# 16-BitSWStatusLed.net
KiCad netlist of a schematic drawn in Altium Designer
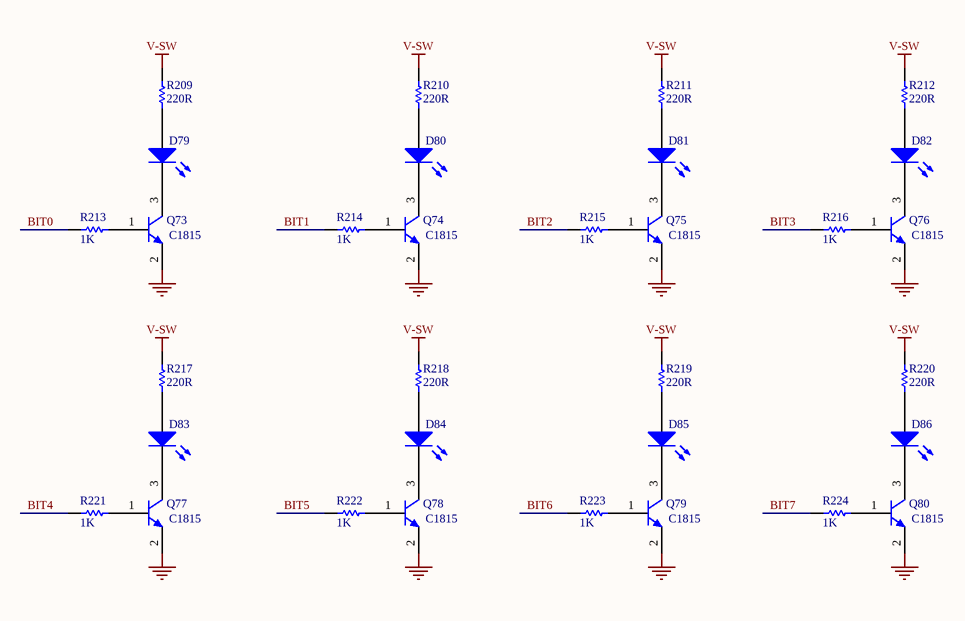
[diagram p0: 16-BitSWStatusLed.SchDoc]

(export (version "E")
  (design (tool "Eeschema 10.0.6"))
  (components
    (comp (ref "D79")
      (value "LED")
      (footprint "LED-3528")
      (description "Typical RED, GREEN, YELLOW, AMBER GaAs LED")
      (fields (field (name "PUBLISHER") "Altium Limited"))
      (libsource (lib "Miscellaneous Devices") (part "LED2"))
    )
    (comp (ref "D80")
      (value "LED")
      (footprint "LED-3528")
      (description "Typical RED, GREEN, YELLOW, AMBER GaAs LED")
      (fields (field (name "PUBLISHER") "Altium Limited"))
      (libsource (lib "Miscellaneous Devices") (part "LED2"))
    )
    (comp (ref "D81")
      (value "LED")
      (footprint "LED-3528")
      (description "Typical RED, GREEN, YELLOW, AMBER GaAs LED")
      (fields (field (name "PUBLISHER") "Altium Limited"))
      (libsource (lib "Miscellaneous Devices") (part "LED2"))
    )
    (comp (ref "D82")
      (value "LED")
      (footprint "LED-3528")
      (description "Typical RED, GREEN, YELLOW, AMBER GaAs LED")
      (fields (field (name "PUBLISHER") "Altium Limited"))
      (libsource (lib "Miscellaneous Devices") (part "LED2"))
    )
    (comp (ref "D83")
      (value "LED")
      (footprint "LED-3528")
      (description "Typical RED, GREEN, YELLOW, AMBER GaAs LED")
      (fields (field (name "PUBLISHER") "Altium Limited"))
      (libsource (lib "Miscellaneous Devices") (part "LED2"))
    )
    (comp (ref "D84")
      (value "LED")
      (footprint "LED-3528")
      (description "Typical RED, GREEN, YELLOW, AMBER GaAs LED")
      (fields (field (name "PUBLISHER") "Altium Limited"))
      (libsource (lib "Miscellaneous Devices") (part "LED2"))
    )
    (comp (ref "D85")
      (value "LED")
      (footprint "LED-3528")
      (description "Typical RED, GREEN, YELLOW, AMBER GaAs LED")
      (fields (field (name "PUBLISHER") "Altium Limited"))
      (libsource (lib "Miscellaneous Devices") (part "LED2"))
    )
    (comp (ref "D86")
      (value "LED")
      (footprint "LED-3528")
      (description "Typical RED, GREEN, YELLOW, AMBER GaAs LED")
      (fields (field (name "PUBLISHER") "Altium Limited"))
      (libsource (lib "Miscellaneous Devices") (part "LED2"))
    )
    (comp (ref "Q73")
      (value "C1815")
      (footprint "SOT23-321")
      (description "NPN Bipolar Transistor")
      (fields (field (name "Comment") "C1815-SMD"))
      (libsource (lib "Miscellaneous Devices") (part "NPN"))
    )
    (comp (ref "Q74")
      (value "C1815")
      (footprint "SOT23-321")
      (description "NPN Bipolar Transistor")
      (fields (field (name "Comment") "C1815-SMD"))
      (libsource (lib "Miscellaneous Devices") (part "NPN"))
    )
    (comp (ref "Q75")
      (value "C1815")
      (footprint "SOT23-321")
      (description "NPN Bipolar Transistor")
      (fields (field (name "Comment") "C1815-SMD"))
      (libsource (lib "Miscellaneous Devices") (part "NPN"))
    )
    (comp (ref "Q76")
      (value "C1815")
      (footprint "SOT23-321")
      (description "NPN Bipolar Transistor")
      (fields (field (name "Comment") "C1815-SMD"))
      (libsource (lib "Miscellaneous Devices") (part "NPN"))
    )
    (comp (ref "Q77")
      (value "C1815")
      (footprint "SOT23-321")
      (description "NPN Bipolar Transistor")
      (fields (field (name "Comment") "C1815-SMD"))
      (libsource (lib "Miscellaneous Devices") (part "NPN"))
    )
    (comp (ref "Q78")
      (value "C1815")
      (footprint "SOT23-321")
      (description "NPN Bipolar Transistor")
      (fields (field (name "Comment") "C1815-SMD"))
      (libsource (lib "Miscellaneous Devices") (part "NPN"))
    )
    (comp (ref "Q79")
      (value "C1815")
      (footprint "SOT23-321")
      (description "NPN Bipolar Transistor")
      (fields (field (name "Comment") "C1815-SMD"))
      (libsource (lib "Miscellaneous Devices") (part "NPN"))
    )
    (comp (ref "Q80")
      (value "C1815")
      (footprint "SOT23-321")
      (description "NPN Bipolar Transistor")
      (fields (field (name "Comment") "C1815-SMD"))
      (libsource (lib "Miscellaneous Devices") (part "NPN"))
    )
    (comp (ref "R209")
      (value "220R")
      (footprint "R-0805")
      (description "Resistor")
      (fields (field (name "Comment") "221") (field (name "PUBLISHER") "Altium Limited"))
      (libsource (lib "Miscellaneous Devices") (part "Res1"))
    )
    (comp (ref "R210")
      (value "220R")
      (footprint "R-0805")
      (description "Resistor")
      (fields (field (name "Comment") "221") (field (name "PUBLISHER") "Altium Limited"))
      (libsource (lib "Miscellaneous Devices") (part "Res1"))
    )
    (comp (ref "R211")
      (value "220R")
      (footprint "R-0805")
      (description "Resistor")
      (fields (field (name "Comment") "221") (field (name "PUBLISHER") "Altium Limited"))
      (libsource (lib "Miscellaneous Devices") (part "Res1"))
    )
    (comp (ref "R212")
      (value "220R")
      (footprint "R-0805")
      (description "Resistor")
      (fields (field (name "Comment") "221") (field (name "PUBLISHER") "Altium Limited"))
      (libsource (lib "Miscellaneous Devices") (part "Res1"))
    )
    (comp (ref "R213")
      (value "1K")
      (footprint "R-0805")
      (description "Resistor")
      (fields (field (name "PUBLISHER") "Altium Limited"))
      (libsource (lib "Miscellaneous Devices") (part "Res1"))
    )
    (comp (ref "R214")
      (value "1K")
      (footprint "R-0805")
      (description "Resistor")
      (fields (field (name "PUBLISHER") "Altium Limited"))
      (libsource (lib "Miscellaneous Devices") (part "Res1"))
    )
    (comp (ref "R215")
      (value "1K")
      (footprint "R-0805")
      (description "Resistor")
      (fields (field (name "PUBLISHER") "Altium Limited"))
      (libsource (lib "Miscellaneous Devices") (part "Res1"))
    )
    (comp (ref "R216")
      (value "1K")
      (footprint "R-0805")
      (description "Resistor")
      (fields (field (name "PUBLISHER") "Altium Limited"))
      (libsource (lib "Miscellaneous Devices") (part "Res1"))
    )
    (comp (ref "R217")
      (value "220R")
      (footprint "R-0805")
      (description "Resistor")
      (fields (field (name "Comment") "221") (field (name "PUBLISHER") "Altium Limited"))
      (libsource (lib "Miscellaneous Devices") (part "Res1"))
    )
    (comp (ref "R218")
      (value "220R")
      (footprint "R-0805")
      (description "Resistor")
      (fields (field (name "Comment") "221") (field (name "PUBLISHER") "Altium Limited"))
      (libsource (lib "Miscellaneous Devices") (part "Res1"))
    )
    (comp (ref "R219")
      (value "220R")
      (footprint "R-0805")
      (description "Resistor")
      (fields (field (name "Comment") "221") (field (name "PUBLISHER") "Altium Limited"))
      (libsource (lib "Miscellaneous Devices") (part "Res1"))
    )
    (comp (ref "R220")
      (value "220R")
      (footprint "R-0805")
      (description "Resistor")
      (fields (field (name "Comment") "221") (field (name "PUBLISHER") "Altium Limited"))
      (libsource (lib "Miscellaneous Devices") (part "Res1"))
    )
    (comp (ref "R221")
      (value "1K")
      (footprint "R-0805")
      (description "Resistor")
      (fields (field (name "PUBLISHER") "Altium Limited"))
      (libsource (lib "Miscellaneous Devices") (part "Res1"))
    )
    (comp (ref "R222")
      (value "1K")
      (footprint "R-0805")
      (description "Resistor")
      (fields (field (name "PUBLISHER") "Altium Limited"))
      (libsource (lib "Miscellaneous Devices") (part "Res1"))
    )
    (comp (ref "R223")
      (value "1K")
      (footprint "R-0805")
      (description "Resistor")
      (fields (field (name "PUBLISHER") "Altium Limited"))
      (libsource (lib "Miscellaneous Devices") (part "Res1"))
    )
    (comp (ref "R224")
      (value "1K")
      (footprint "R-0805")
      (description "Resistor")
      (fields (field (name "PUBLISHER") "Altium Limited"))
      (libsource (lib "Miscellaneous Devices") (part "Res1"))
    )
  )
  (nets
    (net (code "1") (name "/BIT0") (class "Default")
      (node (ref "R213") (pin "2") (pinfunction "2_2") (pintype "passive"))
    )
    (net (code "2") (name "/BIT1") (class "Default")
      (node (ref "R214") (pin "2") (pinfunction "2_2") (pintype "passive"))
    )
    (net (code "3") (name "/BIT2") (class "Default")
      (node (ref "R215") (pin "2") (pinfunction "2_2") (pintype "passive"))
    )
    (net (code "4") (name "/BIT3") (class "Default")
      (node (ref "R216") (pin "2") (pinfunction "2_2") (pintype "passive"))
    )
    (net (code "5") (name "/BIT4") (class "Default")
      (node (ref "R221") (pin "2") (pinfunction "2_2") (pintype "passive"))
    )
    (net (code "6") (name "/BIT5") (class "Default")
      (node (ref "R222") (pin "2") (pinfunction "2_2") (pintype "passive"))
    )
    (net (code "7") (name "/BIT6") (class "Default")
      (node (ref "R223") (pin "2") (pinfunction "2_2") (pintype "passive"))
    )
    (net (code "8") (name "/BIT7") (class "Default")
      (node (ref "R224") (pin "2") (pinfunction "2_2") (pintype "passive"))
    )
    (net (code "9") (name "GND") (class "Default")
      (node (ref "Q73") (pin "2") (pinfunction "E_2") (pintype "passive"))
      (node (ref "Q74") (pin "2") (pinfunction "E_2") (pintype "passive"))
      (node (ref "Q75") (pin "2") (pinfunction "E_2") (pintype "passive"))
      (node (ref "Q76") (pin "2") (pinfunction "E_2") (pintype "passive"))
      (node (ref "Q77") (pin "2") (pinfunction "E_2") (pintype "passive"))
      (node (ref "Q78") (pin "2") (pinfunction "E_2") (pintype "passive"))
      (node (ref "Q79") (pin "2") (pinfunction "E_2") (pintype "passive"))
      (node (ref "Q80") (pin "2") (pinfunction "E_2") (pintype "passive"))
    )
    (net (code "10") (name "Net-(D79-A)") (class "Default")
      (node (ref "D79") (pin "1") (pinfunction "A_1") (pintype "passive"))
      (node (ref "R209") (pin "1") (pinfunction "1_1") (pintype "passive"))
    )
    (net (code "11") (name "Net-(D79-K)") (class "Default")
      (node (ref "D79") (pin "2") (pinfunction "K_2") (pintype "passive"))
      (node (ref "Q73") (pin "3") (pinfunction "C_3") (pintype "passive"))
    )
    (net (code "12") (name "Net-(D80-A)") (class "Default")
      (node (ref "D80") (pin "1") (pinfunction "A_1") (pintype "passive"))
      (node (ref "R210") (pin "1") (pinfunction "1_1") (pintype "passive"))
    )
    (net (code "13") (name "Net-(D80-K)") (class "Default")
      (node (ref "D80") (pin "2") (pinfunction "K_2") (pintype "passive"))
      (node (ref "Q74") (pin "3") (pinfunction "C_3") (pintype "passive"))
    )
    (net (code "14") (name "Net-(D81-A)") (class "Default")
      (node (ref "D81") (pin "1") (pinfunction "A_1") (pintype "passive"))
      (node (ref "R211") (pin "1") (pinfunction "1_1") (pintype "passive"))
    )
    (net (code "15") (name "Net-(D81-K)") (class "Default")
      (node (ref "D81") (pin "2") (pinfunction "K_2") (pintype "passive"))
      (node (ref "Q75") (pin "3") (pinfunction "C_3") (pintype "passive"))
    )
    (net (code "16") (name "Net-(D82-A)") (class "Default")
      (node (ref "D82") (pin "1") (pinfunction "A_1") (pintype "passive"))
      (node (ref "R212") (pin "1") (pinfunction "1_1") (pintype "passive"))
    )
    (net (code "17") (name "Net-(D82-K)") (class "Default")
      (node (ref "D82") (pin "2") (pinfunction "K_2") (pintype "passive"))
      (node (ref "Q76") (pin "3") (pinfunction "C_3") (pintype "passive"))
    )
    (net (code "18") (name "Net-(D83-A)") (class "Default")
      (node (ref "D83") (pin "1") (pinfunction "A_1") (pintype "passive"))
      (node (ref "R217") (pin "1") (pinfunction "1_1") (pintype "passive"))
    )
    (net (code "19") (name "Net-(D83-K)") (class "Default")
      (node (ref "D83") (pin "2") (pinfunction "K_2") (pintype "passive"))
      (node (ref "Q77") (pin "3") (pinfunction "C_3") (pintype "passive"))
    )
    (net (code "20") (name "Net-(D84-A)") (class "Default")
      (node (ref "D84") (pin "1") (pinfunction "A_1") (pintype "passive"))
      (node (ref "R218") (pin "1") (pinfunction "1_1") (pintype "passive"))
    )
    (net (code "21") (name "Net-(D84-K)") (class "Default")
      (node (ref "D84") (pin "2") (pinfunction "K_2") (pintype "passive"))
      (node (ref "Q78") (pin "3") (pinfunction "C_3") (pintype "passive"))
    )
    (net (code "22") (name "Net-(D85-A)") (class "Default")
      (node (ref "D85") (pin "1") (pinfunction "A_1") (pintype "passive"))
      (node (ref "R219") (pin "1") (pinfunction "1_1") (pintype "passive"))
    )
    (net (code "23") (name "Net-(D85-K)") (class "Default")
      (node (ref "D85") (pin "2") (pinfunction "K_2") (pintype "passive"))
      (node (ref "Q79") (pin "3") (pinfunction "C_3") (pintype "passive"))
    )
    (net (code "24") (name "Net-(D86-A)") (class "Default")
      (node (ref "D86") (pin "1") (pinfunction "A_1") (pintype "passive"))
      (node (ref "R220") (pin "1") (pinfunction "1_1") (pintype "passive"))
    )
    (net (code "25") (name "Net-(D86-K)") (class "Default")
      (node (ref "D86") (pin "2") (pinfunction "K_2") (pintype "passive"))
      (node (ref "Q80") (pin "3") (pinfunction "C_3") (pintype "passive"))
    )
    (net (code "26") (name "Net-(Q73-B)") (class "Default")
      (node (ref "Q73") (pin "1") (pinfunction "B_1") (pintype "passive"))
      (node (ref "R213") (pin "1") (pinfunction "1_1") (pintype "passive"))
    )
    (net (code "27") (name "Net-(Q74-B)") (class "Default")
      (node (ref "Q74") (pin "1") (pinfunction "B_1") (pintype "passive"))
      (node (ref "R214") (pin "1") (pinfunction "1_1") (pintype "passive"))
    )
    (net (code "28") (name "Net-(Q75-B)") (class "Default")
      (node (ref "Q75") (pin "1") (pinfunction "B_1") (pintype "passive"))
      (node (ref "R215") (pin "1") (pinfunction "1_1") (pintype "passive"))
    )
    (net (code "29") (name "Net-(Q76-B)") (class "Default")
      (node (ref "Q76") (pin "1") (pinfunction "B_1") (pintype "passive"))
      (node (ref "R216") (pin "1") (pinfunction "1_1") (pintype "passive"))
    )
    (net (code "30") (name "Net-(Q77-B)") (class "Default")
      (node (ref "Q77") (pin "1") (pinfunction "B_1") (pintype "passive"))
      (node (ref "R221") (pin "1") (pinfunction "1_1") (pintype "passive"))
    )
    (net (code "31") (name "Net-(Q78-B)") (class "Default")
      (node (ref "Q78") (pin "1") (pinfunction "B_1") (pintype "passive"))
      (node (ref "R222") (pin "1") (pinfunction "1_1") (pintype "passive"))
    )
    (net (code "32") (name "Net-(Q79-B)") (class "Default")
      (node (ref "Q79") (pin "1") (pinfunction "B_1") (pintype "passive"))
      (node (ref "R223") (pin "1") (pinfunction "1_1") (pintype "passive"))
    )
    (net (code "33") (name "Net-(Q80-B)") (class "Default")
      (node (ref "Q80") (pin "1") (pinfunction "B_1") (pintype "passive"))
      (node (ref "R224") (pin "1") (pinfunction "1_1") (pintype "passive"))
    )
    (net (code "34") (name "V-SW") (class "Default")
      (node (ref "R209") (pin "2") (pinfunction "2_2") (pintype "passive"))
      (node (ref "R210") (pin "2") (pinfunction "2_2") (pintype "passive"))
      (node (ref "R211") (pin "2") (pinfunction "2_2") (pintype "passive"))
      (node (ref "R212") (pin "2") (pinfunction "2_2") (pintype "passive"))
      (node (ref "R217") (pin "2") (pinfunction "2_2") (pintype "passive"))
      (node (ref "R218") (pin "2") (pinfunction "2_2") (pintype "passive"))
      (node (ref "R219") (pin "2") (pinfunction "2_2") (pintype "passive"))
      (node (ref "R220") (pin "2") (pinfunction "2_2") (pintype "passive"))
    )
  )
)
